# universal-i2c-sensor-master-unit.net
KiCad netlist of a schematic drawn in EAGLE
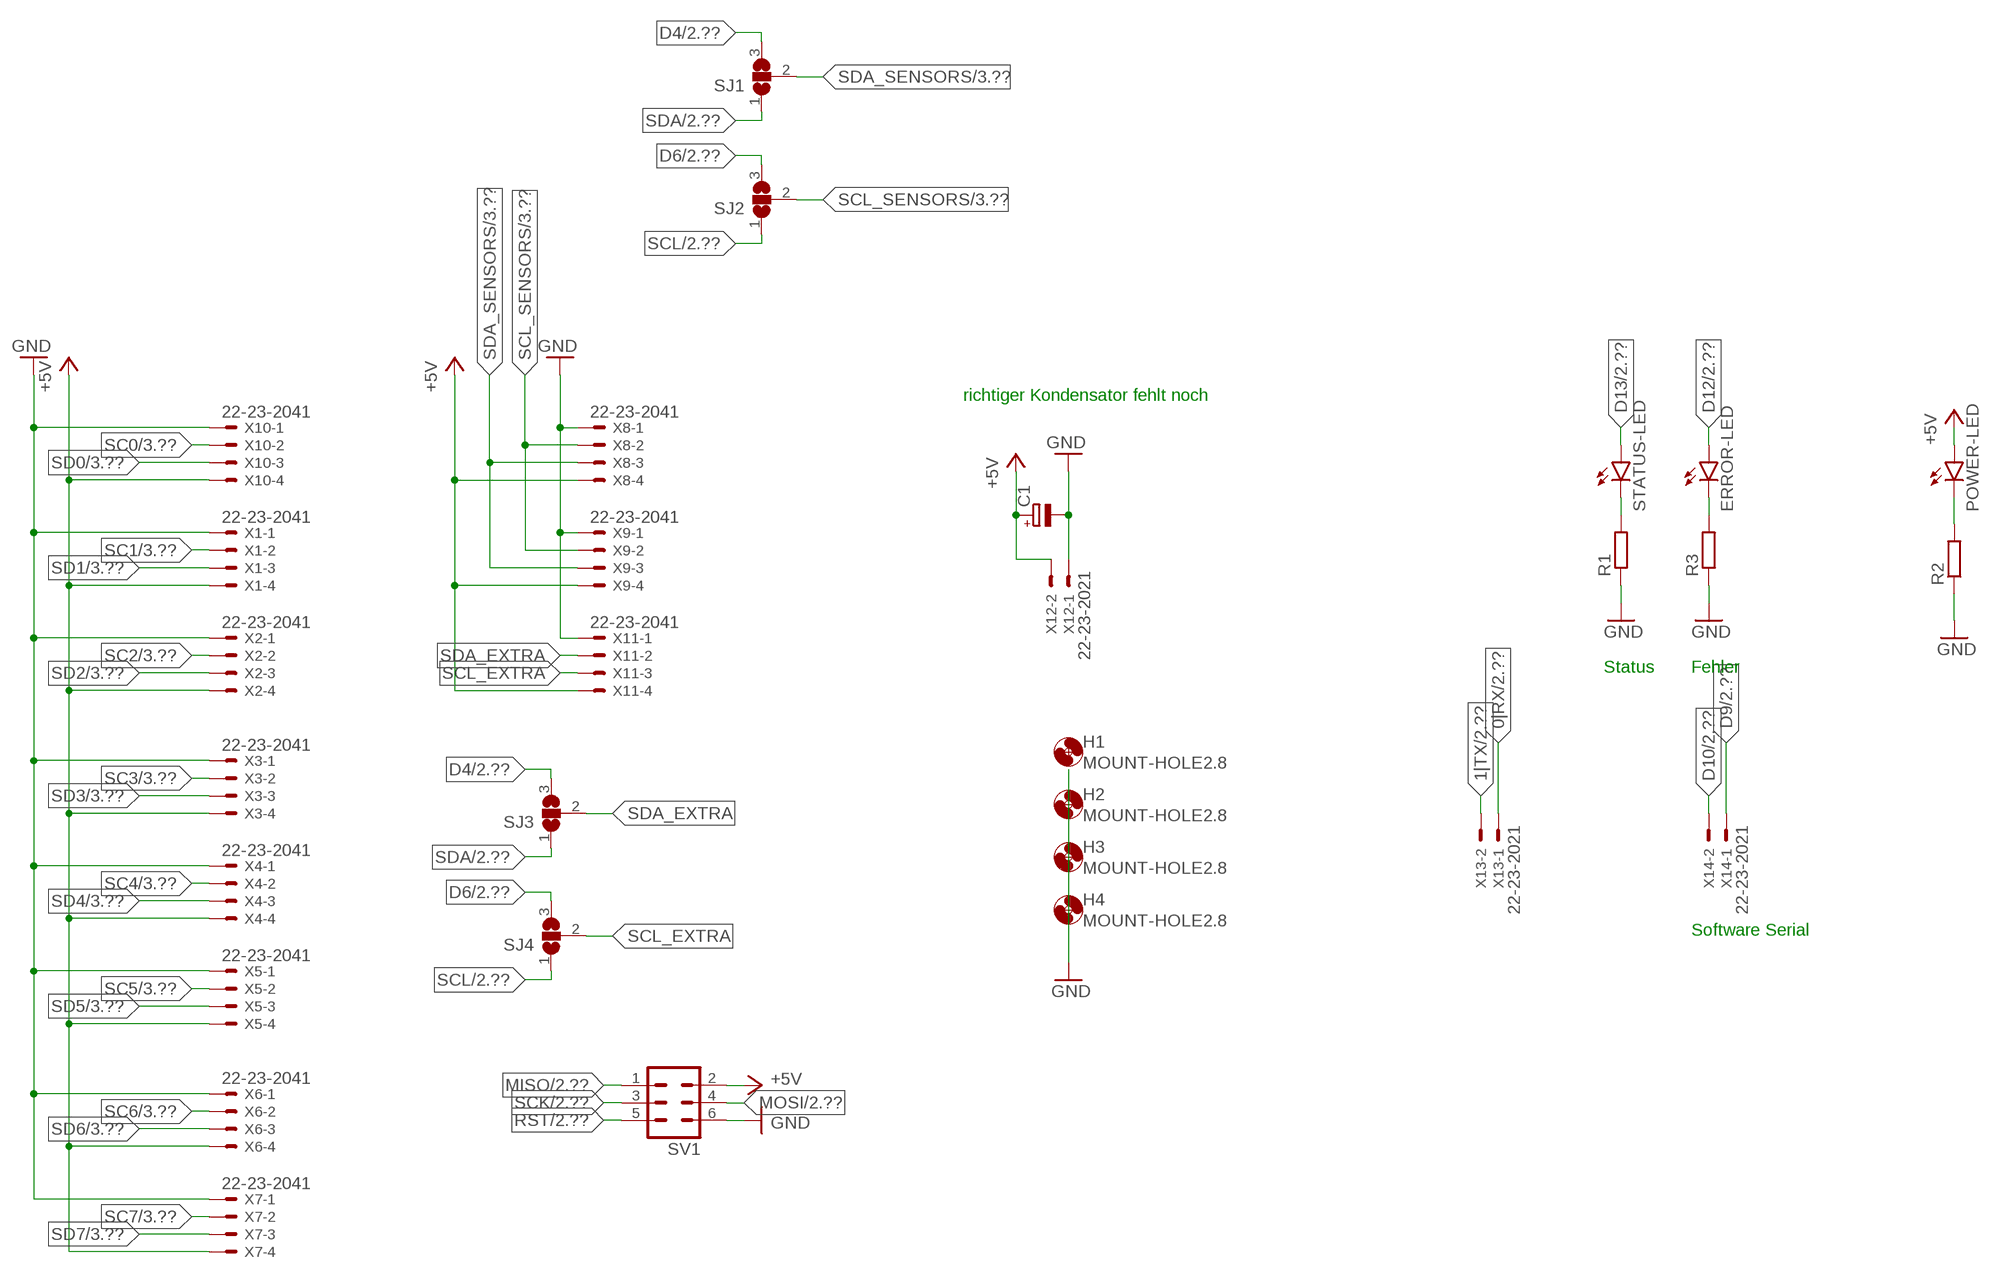
[diagram p0: schematic, sheet 1]
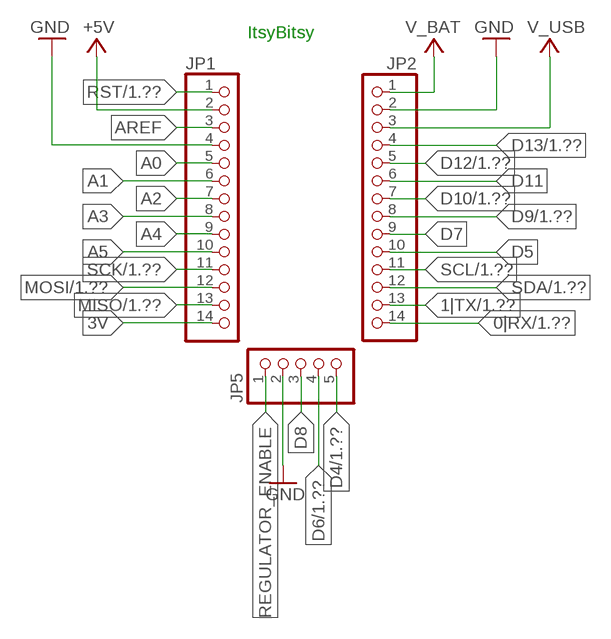
[diagram p1: schematic, sheet 2]
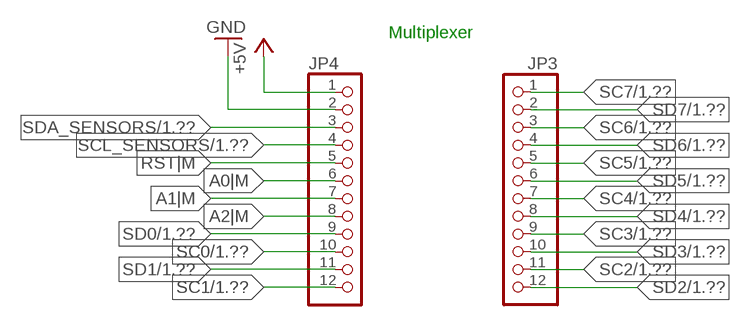
[diagram p2: schematic, sheet 3]

(export (version "E")
  (design (tool "Eeschema 10.0.6"))
  (components
    (comp (ref "C1")
      (value "CPOL-EUE2.5-6")
      (footprint "eagle-import:E2,5-6")
      (libsource (lib "eagle-import") (part "CPOL-EUE2.5-6"))
    )
    (comp (ref "ERROR-LED")
      (value "LED3MM")
      (footprint "eagle-import:LED3MM")
      (libsource (lib "eagle-import") (part "LED3MM"))
    )
    (comp (ref "H1")
      (value "MOUNT-HOLE2.8")
      (footprint "eagle-import:2,8")
      (libsource (lib "eagle-import") (part "MOUNT-HOLE2.8"))
    )
    (comp (ref "H2")
      (value "MOUNT-HOLE2.8")
      (footprint "eagle-import:2,8")
      (libsource (lib "eagle-import") (part "MOUNT-HOLE2.8"))
    )
    (comp (ref "H3")
      (value "MOUNT-HOLE2.8")
      (footprint "eagle-import:2,8")
      (libsource (lib "eagle-import") (part "MOUNT-HOLE2.8"))
    )
    (comp (ref "H4")
      (value "MOUNT-HOLE2.8")
      (footprint "eagle-import:2,8")
      (libsource (lib "eagle-import") (part "MOUNT-HOLE2.8"))
    )
    (comp (ref "POWER-LED")
      (value "LED3MM")
      (footprint "eagle-import:LED3MM")
      (libsource (lib "eagle-import") (part "LED3MM"))
    )
    (comp (ref "R1")
      (value "R-EU_0207/10")
      (footprint "eagle-import:0207_10")
      (libsource (lib "eagle-import") (part "R-EU_0207/10"))
    )
    (comp (ref "R2")
      (value "R-EU_0207/10")
      (footprint "eagle-import:0207_10")
      (libsource (lib "eagle-import") (part "R-EU_0207/10"))
    )
    (comp (ref "R3")
      (value "R-EU_0207/10")
      (footprint "eagle-import:0207_10")
      (libsource (lib "eagle-import") (part "R-EU_0207/10"))
    )
    (comp (ref "SJ1")
      (value "SJ2W")
      (footprint "eagle-import:SJ_2")
      (libsource (lib "eagle-import") (part "SJ2W"))
    )
    (comp (ref "SJ2")
      (value "SJ2W")
      (footprint "eagle-import:SJ_2")
      (libsource (lib "eagle-import") (part "SJ2W"))
    )
    (comp (ref "SJ3")
      (value "SJ2W")
      (footprint "eagle-import:SJ_2")
      (libsource (lib "eagle-import") (part "SJ2W"))
    )
    (comp (ref "SJ4")
      (value "SJ2W")
      (footprint "eagle-import:SJ_2")
      (libsource (lib "eagle-import") (part "SJ2W"))
    )
    (comp (ref "STATUS-LED")
      (value "LED3MM")
      (footprint "eagle-import:LED3MM")
      (libsource (lib "eagle-import") (part "LED3MM"))
    )
    (comp (ref "SV1")
      (value "MA03-2")
      (footprint "eagle-import:MA03-2")
      (libsource (lib "eagle-import") (part "MA03-2"))
    )
    (comp (ref "X1")
      (value "22-23-2041")
      (footprint "eagle-import:22-23-2041")
      (fields (field (name "MF") "MOLEX"))
      (libsource (lib "eagle-import") (part "22-23-2041"))
    )
    (comp (ref "X2")
      (value "22-23-2041")
      (footprint "eagle-import:22-23-2041")
      (fields (field (name "MF") "MOLEX"))
      (libsource (lib "eagle-import") (part "22-23-2041"))
    )
    (comp (ref "X3")
      (value "22-23-2041")
      (footprint "eagle-import:22-23-2041")
      (fields (field (name "MF") "MOLEX"))
      (libsource (lib "eagle-import") (part "22-23-2041"))
    )
    (comp (ref "X4")
      (value "22-23-2041")
      (footprint "eagle-import:22-23-2041")
      (fields (field (name "MF") "MOLEX"))
      (libsource (lib "eagle-import") (part "22-23-2041"))
    )
    (comp (ref "X5")
      (value "22-23-2041")
      (footprint "eagle-import:22-23-2041")
      (fields (field (name "MF") "MOLEX"))
      (libsource (lib "eagle-import") (part "22-23-2041"))
    )
    (comp (ref "X6")
      (value "22-23-2041")
      (footprint "eagle-import:22-23-2041")
      (fields (field (name "MF") "MOLEX"))
      (libsource (lib "eagle-import") (part "22-23-2041"))
    )
    (comp (ref "X7")
      (value "22-23-2041")
      (footprint "eagle-import:22-23-2041")
      (fields (field (name "MF") "MOLEX"))
      (libsource (lib "eagle-import") (part "22-23-2041"))
    )
    (comp (ref "X8")
      (value "22-23-2041")
      (footprint "eagle-import:22-23-2041")
      (fields (field (name "MF") "MOLEX"))
      (libsource (lib "eagle-import") (part "22-23-2041"))
    )
    (comp (ref "X9")
      (value "22-23-2041")
      (footprint "eagle-import:22-23-2041")
      (fields (field (name "MF") "MOLEX"))
      (libsource (lib "eagle-import") (part "22-23-2041"))
    )
    (comp (ref "X10")
      (value "22-23-2041")
      (footprint "eagle-import:22-23-2041")
      (fields (field (name "MF") "MOLEX"))
      (libsource (lib "eagle-import") (part "22-23-2041"))
    )
    (comp (ref "X11")
      (value "22-23-2041")
      (footprint "eagle-import:22-23-2041")
      (fields (field (name "MF") "MOLEX"))
      (libsource (lib "eagle-import") (part "22-23-2041"))
    )
    (comp (ref "X12")
      (value "22-23-2021")
      (footprint "eagle-import:22-23-2021")
      (fields (field (name "MF") "MOLEX"))
      (libsource (lib "eagle-import") (part "22-23-2021"))
    )
    (comp (ref "X13")
      (value "22-23-2021")
      (footprint "eagle-import:22-23-2021")
      (fields (field (name "MF") "MOLEX"))
      (libsource (lib "eagle-import") (part "22-23-2021"))
    )
    (comp (ref "X14")
      (value "22-23-2021")
      (footprint "eagle-import:22-23-2021")
      (fields (field (name "MF") "MOLEX"))
      (libsource (lib "eagle-import") (part "22-23-2021"))
    )
    (comp (ref "JP3")
      (value "PINHD-1X12")
      (footprint "eagle-import:1X12")
      (libsource (lib "eagle-import") (part "PINHD-1X12"))
    )
    (comp (ref "JP4")
      (value "PINHD-1X12")
      (footprint "eagle-import:1X12")
      (libsource (lib "eagle-import") (part "PINHD-1X12"))
    )
    (comp (ref "JP1")
      (value "PINHD-1X14")
      (footprint "eagle-import:1X14")
      (libsource (lib "eagle-import") (part "PINHD-1X14"))
    )
    (comp (ref "JP2")
      (value "PINHD-1X14")
      (footprint "eagle-import:1X14")
      (libsource (lib "eagle-import") (part "PINHD-1X14"))
    )
    (comp (ref "JP5")
      (value "PINHD-1X5")
      (footprint "eagle-import:1X05")
      (libsource (lib "eagle-import") (part "PINHD-1X5"))
    )
  )
  (nets
    (net (code "1") (name "+5V") (class "Default")
      (node (ref "C1") (pin "+") (pinfunction "+_+") (pintype "passive"))
      (node (ref "JP1") (pin "2") (pinfunction "2_2") (pintype "passive"))
      (node (ref "JP4") (pin "1") (pinfunction "1_1") (pintype "passive"))
      (node (ref "POWER-LED") (pin "A") (pinfunction "A_A") (pintype "passive"))
      (node (ref "SV1") (pin "2") (pinfunction "2_2") (pintype "passive"))
      (node (ref "X1") (pin "4") (pinfunction "S_4") (pintype "passive"))
      (node (ref "X10") (pin "4") (pinfunction "S_4") (pintype "passive"))
      (node (ref "X11") (pin "4") (pinfunction "S_4") (pintype "passive"))
      (node (ref "X12") (pin "2") (pinfunction "S_2") (pintype "passive"))
      (node (ref "X2") (pin "4") (pinfunction "S_4") (pintype "passive"))
      (node (ref "X3") (pin "4") (pinfunction "S_4") (pintype "passive"))
      (node (ref "X4") (pin "4") (pinfunction "S_4") (pintype "passive"))
      (node (ref "X5") (pin "4") (pinfunction "S_4") (pintype "passive"))
      (node (ref "X6") (pin "4") (pinfunction "S_4") (pintype "passive"))
      (node (ref "X7") (pin "4") (pinfunction "S_4") (pintype "passive"))
      (node (ref "X8") (pin "4") (pinfunction "S_4") (pintype "passive"))
      (node (ref "X9") (pin "4") (pinfunction "S_4") (pintype "passive"))
    )
    (net (code "2") (name "0|RX") (class "Default")
      (node (ref "JP2") (pin "14") (pinfunction "14_14") (pintype "passive"))
      (node (ref "X13") (pin "1") (pinfunction "S_1") (pintype "passive"))
    )
    (net (code "3") (name "1|TX") (class "Default")
      (node (ref "JP2") (pin "13") (pinfunction "13_13") (pintype "passive"))
      (node (ref "X13") (pin "2") (pinfunction "S_2") (pintype "passive"))
    )
    (net (code "4") (name "3V") (class "Default")
      (node (ref "JP1") (pin "14") (pinfunction "14_14") (pintype "passive"))
    )
    (net (code "5") (name "A0") (class "Default")
      (node (ref "JP1") (pin "5") (pinfunction "5_5") (pintype "passive"))
    )
    (net (code "6") (name "A0|M") (class "Default")
      (node (ref "JP4") (pin "6") (pinfunction "6_6") (pintype "passive"))
    )
    (net (code "7") (name "A1") (class "Default")
      (node (ref "JP1") (pin "6") (pinfunction "6_6") (pintype "passive"))
    )
    (net (code "8") (name "A1|M") (class "Default")
      (node (ref "JP4") (pin "7") (pinfunction "7_7") (pintype "passive"))
    )
    (net (code "9") (name "A2") (class "Default")
      (node (ref "JP1") (pin "7") (pinfunction "7_7") (pintype "passive"))
    )
    (net (code "10") (name "A2|M") (class "Default")
      (node (ref "JP4") (pin "8") (pinfunction "8_8") (pintype "passive"))
    )
    (net (code "11") (name "A3") (class "Default")
      (node (ref "JP1") (pin "8") (pinfunction "8_8") (pintype "passive"))
    )
    (net (code "12") (name "A4") (class "Default")
      (node (ref "JP1") (pin "9") (pinfunction "9_9") (pintype "passive"))
    )
    (net (code "13") (name "A5") (class "Default")
      (node (ref "JP1") (pin "10") (pinfunction "10_10") (pintype "passive"))
    )
    (net (code "14") (name "AREF") (class "Default")
      (node (ref "JP1") (pin "3") (pinfunction "3_3") (pintype "passive"))
    )
    (net (code "15") (name "D4") (class "Default")
      (node (ref "JP5") (pin "5") (pinfunction "5_5") (pintype "passive"))
      (node (ref "SJ1") (pin "3") (pinfunction "3_3") (pintype "passive"))
      (node (ref "SJ3") (pin "3") (pinfunction "3_3") (pintype "passive"))
    )
    (net (code "16") (name "D5") (class "Default")
      (node (ref "JP2") (pin "10") (pinfunction "10_10") (pintype "passive"))
    )
    (net (code "17") (name "D6") (class "Default")
      (node (ref "JP5") (pin "4") (pinfunction "4_4") (pintype "passive"))
      (node (ref "SJ2") (pin "3") (pinfunction "3_3") (pintype "passive"))
      (node (ref "SJ4") (pin "3") (pinfunction "3_3") (pintype "passive"))
    )
    (net (code "18") (name "D7") (class "Default")
      (node (ref "JP2") (pin "9") (pinfunction "9_9") (pintype "passive"))
    )
    (net (code "19") (name "D8") (class "Default")
      (node (ref "JP5") (pin "3") (pinfunction "3_3") (pintype "passive"))
    )
    (net (code "20") (name "D9") (class "Default")
      (node (ref "JP2") (pin "8") (pinfunction "8_8") (pintype "passive"))
      (node (ref "X14") (pin "1") (pinfunction "S_1") (pintype "passive"))
    )
    (net (code "21") (name "D10") (class "Default")
      (node (ref "JP2") (pin "7") (pinfunction "7_7") (pintype "passive"))
      (node (ref "X14") (pin "2") (pinfunction "S_2") (pintype "passive"))
    )
    (net (code "22") (name "D11") (class "Default")
      (node (ref "JP2") (pin "6") (pinfunction "6_6") (pintype "passive"))
    )
    (net (code "23") (name "D12") (class "Default")
      (node (ref "ERROR-LED") (pin "A") (pinfunction "A_A") (pintype "passive"))
      (node (ref "JP2") (pin "5") (pinfunction "5_5") (pintype "passive"))
    )
    (net (code "24") (name "D13") (class "Default")
      (node (ref "JP2") (pin "4") (pinfunction "4_4") (pintype "passive"))
      (node (ref "STATUS-LED") (pin "A") (pinfunction "A_A") (pintype "passive"))
    )
    (net (code "25") (name "GND") (class "Default")
      (node (ref "C1") (pin "-") (pinfunction "-_-") (pintype "passive"))
      (node (ref "JP1") (pin "4") (pinfunction "4_4") (pintype "passive"))
      (node (ref "JP2") (pin "2") (pinfunction "2_2") (pintype "passive"))
      (node (ref "JP4") (pin "2") (pinfunction "2_2") (pintype "passive"))
      (node (ref "JP5") (pin "2") (pinfunction "2_2") (pintype "passive"))
      (node (ref "R1") (pin "1") (pinfunction "1_1") (pintype "passive"))
      (node (ref "R2") (pin "1") (pinfunction "1_1") (pintype "passive"))
      (node (ref "R3") (pin "1") (pinfunction "1_1") (pintype "passive"))
      (node (ref "SV1") (pin "6") (pinfunction "6_6") (pintype "passive"))
      (node (ref "X1") (pin "1") (pinfunction "S_1") (pintype "passive"))
      (node (ref "X10") (pin "1") (pinfunction "S_1") (pintype "passive"))
      (node (ref "X11") (pin "1") (pinfunction "S_1") (pintype "passive"))
      (node (ref "X12") (pin "1") (pinfunction "S_1") (pintype "passive"))
      (node (ref "X2") (pin "1") (pinfunction "S_1") (pintype "passive"))
      (node (ref "X3") (pin "1") (pinfunction "S_1") (pintype "passive"))
      (node (ref "X4") (pin "1") (pinfunction "S_1") (pintype "passive"))
      (node (ref "X5") (pin "1") (pinfunction "S_1") (pintype "passive"))
      (node (ref "X6") (pin "1") (pinfunction "S_1") (pintype "passive"))
      (node (ref "X7") (pin "1") (pinfunction "S_1") (pintype "passive"))
      (node (ref "X8") (pin "1") (pinfunction "S_1") (pintype "passive"))
      (node (ref "X9") (pin "1") (pinfunction "S_1") (pintype "passive"))
    )
    (net (code "26") (name "MISO") (class "Default")
      (node (ref "JP1") (pin "13") (pinfunction "13_13") (pintype "passive"))
      (node (ref "SV1") (pin "1") (pinfunction "1_1") (pintype "passive"))
    )
    (net (code "27") (name "MOSI") (class "Default")
      (node (ref "JP1") (pin "12") (pinfunction "12_12") (pintype "passive"))
      (node (ref "SV1") (pin "4") (pinfunction "4_4") (pintype "passive"))
    )
    (net (code "28") (name "Net-(ERROR-LED-C)") (class "Default")
      (node (ref "ERROR-LED") (pin "K") (pinfunction "C_K") (pintype "passive"))
      (node (ref "R3") (pin "2") (pinfunction "2_2") (pintype "passive"))
    )
    (net (code "29") (name "Net-(POWER-LED-C)") (class "Default")
      (node (ref "POWER-LED") (pin "K") (pinfunction "C_K") (pintype "passive"))
      (node (ref "R2") (pin "2") (pinfunction "2_2") (pintype "passive"))
    )
    (net (code "30") (name "Net-(STATUS-LED-C)") (class "Default")
      (node (ref "R1") (pin "2") (pinfunction "2_2") (pintype "passive"))
      (node (ref "STATUS-LED") (pin "K") (pinfunction "C_K") (pintype "passive"))
    )
    (net (code "31") (name "REGULATOR_ENABLE") (class "Default")
      (node (ref "JP5") (pin "1") (pinfunction "1_1") (pintype "passive"))
    )
    (net (code "32") (name "RST") (class "Default")
      (node (ref "JP1") (pin "1") (pinfunction "1_1") (pintype "passive"))
      (node (ref "SV1") (pin "5") (pinfunction "5_5") (pintype "passive"))
    )
    (net (code "33") (name "RST|M") (class "Default")
      (node (ref "JP4") (pin "5") (pinfunction "5_5") (pintype "passive"))
    )
    (net (code "34") (name "SC0") (class "Default")
      (node (ref "JP4") (pin "10") (pinfunction "10_10") (pintype "passive"))
      (node (ref "X10") (pin "2") (pinfunction "S_2") (pintype "passive"))
    )
    (net (code "35") (name "SC1") (class "Default")
      (node (ref "JP4") (pin "12") (pinfunction "12_12") (pintype "passive"))
      (node (ref "X1") (pin "2") (pinfunction "S_2") (pintype "passive"))
    )
    (net (code "36") (name "SC2") (class "Default")
      (node (ref "JP3") (pin "11") (pinfunction "11_11") (pintype "passive"))
      (node (ref "X2") (pin "2") (pinfunction "S_2") (pintype "passive"))
    )
    (net (code "37") (name "SC3") (class "Default")
      (node (ref "JP3") (pin "9") (pinfunction "9_9") (pintype "passive"))
      (node (ref "X3") (pin "2") (pinfunction "S_2") (pintype "passive"))
    )
    (net (code "38") (name "SC4") (class "Default")
      (node (ref "JP3") (pin "7") (pinfunction "7_7") (pintype "passive"))
      (node (ref "X4") (pin "2") (pinfunction "S_2") (pintype "passive"))
    )
    (net (code "39") (name "SC5") (class "Default")
      (node (ref "JP3") (pin "5") (pinfunction "5_5") (pintype "passive"))
      (node (ref "X5") (pin "2") (pinfunction "S_2") (pintype "passive"))
    )
    (net (code "40") (name "SC6") (class "Default")
      (node (ref "JP3") (pin "3") (pinfunction "3_3") (pintype "passive"))
      (node (ref "X6") (pin "2") (pinfunction "S_2") (pintype "passive"))
    )
    (net (code "41") (name "SC7") (class "Default")
      (node (ref "JP3") (pin "1") (pinfunction "1_1") (pintype "passive"))
      (node (ref "X7") (pin "2") (pinfunction "S_2") (pintype "passive"))
    )
    (net (code "42") (name "SCK") (class "Default")
      (node (ref "JP1") (pin "11") (pinfunction "11_11") (pintype "passive"))
      (node (ref "SV1") (pin "3") (pinfunction "3_3") (pintype "passive"))
    )
    (net (code "43") (name "SCL") (class "Default")
      (node (ref "JP2") (pin "11") (pinfunction "11_11") (pintype "passive"))
      (node (ref "SJ2") (pin "1") (pinfunction "1_1") (pintype "passive"))
      (node (ref "SJ4") (pin "1") (pinfunction "1_1") (pintype "passive"))
    )
    (net (code "44") (name "SCL_EXTRA") (class "Default")
      (node (ref "SJ4") (pin "2") (pinfunction "2_2") (pintype "passive"))
      (node (ref "X11") (pin "3") (pinfunction "S_3") (pintype "passive"))
    )
    (net (code "45") (name "SCL_SENSORS") (class "Default")
      (node (ref "JP4") (pin "4") (pinfunction "4_4") (pintype "passive"))
      (node (ref "SJ2") (pin "2") (pinfunction "2_2") (pintype "passive"))
      (node (ref "X8") (pin "2") (pinfunction "S_2") (pintype "passive"))
      (node (ref "X9") (pin "2") (pinfunction "S_2") (pintype "passive"))
    )
    (net (code "46") (name "SD0") (class "Default")
      (node (ref "JP4") (pin "9") (pinfunction "9_9") (pintype "passive"))
      (node (ref "X10") (pin "3") (pinfunction "S_3") (pintype "passive"))
    )
    (net (code "47") (name "SD1") (class "Default")
      (node (ref "JP4") (pin "11") (pinfunction "11_11") (pintype "passive"))
      (node (ref "X1") (pin "3") (pinfunction "S_3") (pintype "passive"))
    )
    (net (code "48") (name "SD2") (class "Default")
      (node (ref "JP3") (pin "12") (pinfunction "12_12") (pintype "passive"))
      (node (ref "X2") (pin "3") (pinfunction "S_3") (pintype "passive"))
    )
    (net (code "49") (name "SD3") (class "Default")
      (node (ref "JP3") (pin "10") (pinfunction "10_10") (pintype "passive"))
      (node (ref "X3") (pin "3") (pinfunction "S_3") (pintype "passive"))
    )
    (net (code "50") (name "SD4") (class "Default")
      (node (ref "JP3") (pin "8") (pinfunction "8_8") (pintype "passive"))
      (node (ref "X4") (pin "3") (pinfunction "S_3") (pintype "passive"))
    )
    (net (code "51") (name "SD5") (class "Default")
      (node (ref "JP3") (pin "6") (pinfunction "6_6") (pintype "passive"))
      (node (ref "X5") (pin "3") (pinfunction "S_3") (pintype "passive"))
    )
    (net (code "52") (name "SD6") (class "Default")
      (node (ref "JP3") (pin "4") (pinfunction "4_4") (pintype "passive"))
      (node (ref "X6") (pin "3") (pinfunction "S_3") (pintype "passive"))
    )
    (net (code "53") (name "SD7") (class "Default")
      (node (ref "JP3") (pin "2") (pinfunction "2_2") (pintype "passive"))
      (node (ref "X7") (pin "3") (pinfunction "S_3") (pintype "passive"))
    )
    (net (code "54") (name "SDA") (class "Default")
      (node (ref "JP2") (pin "12") (pinfunction "12_12") (pintype "passive"))
      (node (ref "SJ1") (pin "1") (pinfunction "1_1") (pintype "passive"))
      (node (ref "SJ3") (pin "1") (pinfunction "1_1") (pintype "passive"))
    )
    (net (code "55") (name "SDA_EXTRA") (class "Default")
      (node (ref "SJ3") (pin "2") (pinfunction "2_2") (pintype "passive"))
      (node (ref "X11") (pin "2") (pinfunction "S_2") (pintype "passive"))
    )
    (net (code "56") (name "SDA_SENSORS") (class "Default")
      (node (ref "JP4") (pin "3") (pinfunction "3_3") (pintype "passive"))
      (node (ref "SJ1") (pin "2") (pinfunction "2_2") (pintype "passive"))
      (node (ref "X8") (pin "3") (pinfunction "S_3") (pintype "passive"))
      (node (ref "X9") (pin "3") (pinfunction "S_3") (pintype "passive"))
    )
    (net (code "57") (name "V_BAT") (class "Default")
      (node (ref "JP2") (pin "1") (pinfunction "1_1") (pintype "passive"))
    )
    (net (code "58") (name "V_USB") (class "Default")
      (node (ref "JP2") (pin "3") (pinfunction "3_3") (pintype "passive"))
    )
  )
)
